# Quadrature_Decoder.net
KiCad netlist of a schematic drawn in Altium Designer
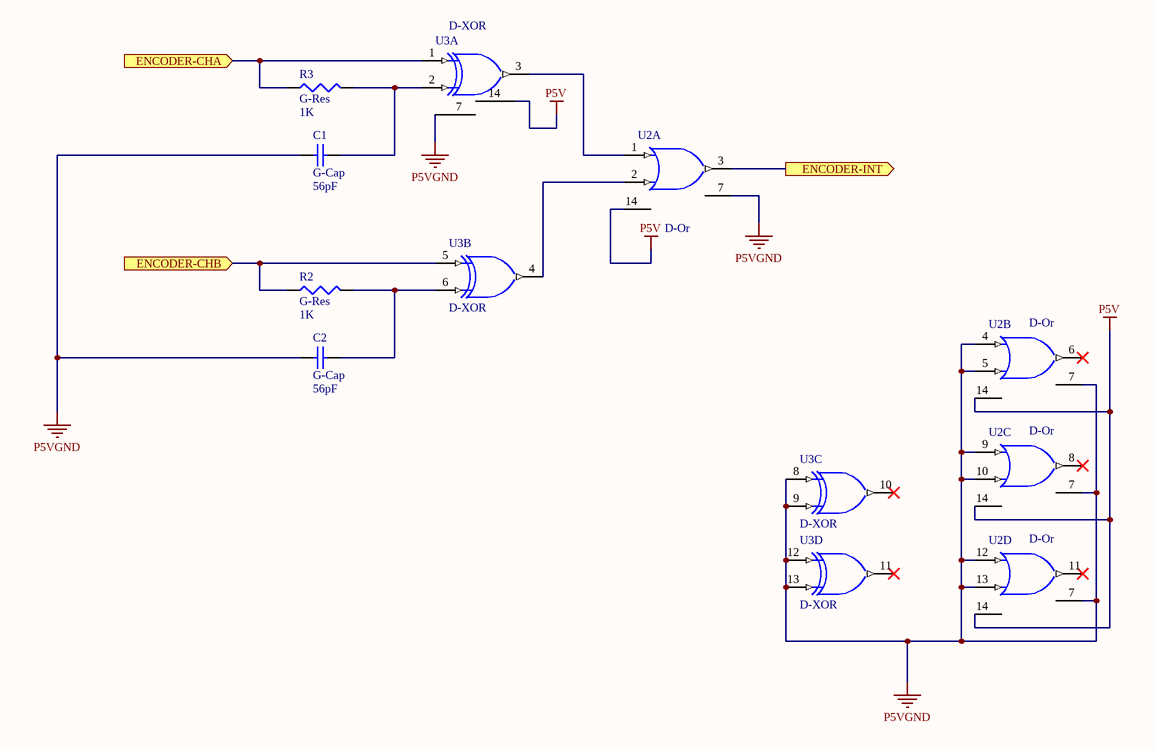
[diagram p0: Quadrature Decoder.SchDoc]

(export (version "E")
  (design (tool "Eeschema 10.0.6"))
  (components
    (comp (ref "C1")
      (value "G-Cap")
      (footprint "Cap2.54mm_LGE1.0")
      (description "capacitor (specify value)")
      (fields (field (name "ALTIUM_VALUE") "56pF") (field (name "PUBLISHER") "Altium Limited"))
      (libsource (lib "PartsDatabaseV13p4") (part "G-Cap"))
    )
    (comp (ref "C2")
      (value "G-Cap")
      (footprint "Cap2.54mm_LGE1.0")
      (description "capacitor (specify value)")
      (fields (field (name "ALTIUM_VALUE") "56pF") (field (name "PUBLISHER") "Altium Limited"))
      (libsource (lib "PartsDatabaseV13p4") (part "G-Cap"))
    )
    (comp (ref "R2")
      (value "G-Res")
      (footprint "Res2.54mm_LGE1.0")
      (description "resistor (specify value)")
      (fields (field (name "ALTIUM_VALUE") "1K") (field (name "PUBLISHER") "Altium Limited"))
      (libsource (lib "PartsDatabaseV13p4") (part "G-Res"))
    )
    (comp (ref "R3")
      (value "G-Res")
      (footprint "Res2.54mm_LGE1.0")
      (description "resistor (specify value)")
      (fields (field (name "ALTIUM_VALUE") "1K") (field (name "PUBLISHER") "Altium Limited"))
      (libsource (lib "PartsDatabaseV13p4") (part "G-Res"))
    )
    (comp (ref "U2")
      (value "D-Or")
      (footprint "DIP14_LGE1.0")
      (description "quad 2-input OR gate")
      (fields (field (name "PUBLISHER") "Altium Limited"))
      (libsource (lib "PartsDatabaseV13p4") (part "D-Or"))
    )
    (comp (ref "U3")
      (value "D-XOR")
      (footprint "DIP14_LGE1.0")
      (description "CD4070B")
      (libsource (lib "PartsDatabaseV13p4") (part "D-XOR"))
    )
  )
  (nets
    (net (code "1") (name "/ENCODER-CHA") (class "Default")
      (node (ref "R3") (pin "1") (pinfunction "1_1") (pintype "passive"))
      (node (ref "U3") (pin "1") (pinfunction "A_1") (pintype "input"))
    )
    (net (code "2") (name "/ENCODER-CHB") (class "Default")
      (node (ref "R2") (pin "1") (pinfunction "1_1") (pintype "passive"))
      (node (ref "U3") (pin "5") (pinfunction "C_5") (pintype "input"))
    )
    (net (code "3") (name "/ENCODER-INT") (class "Default")
      (node (ref "U2") (pin "3") (pinfunction "Y_3") (pintype "output"))
    )
    (net (code "4") (name "Net-(U2A-A)") (class "Default")
      (node (ref "U2") (pin "1") (pinfunction "A_1") (pintype "input"))
      (node (ref "U3") (pin "3") (pinfunction "J_3") (pintype "output"))
    )
    (net (code "5") (name "Net-(U2A-B)") (class "Default")
      (node (ref "U2") (pin "2") (pinfunction "B_2") (pintype "input"))
      (node (ref "U3") (pin "4") (pinfunction "K_4") (pintype "output"))
    )
    (net (code "6") (name "Net-(U3A-B)") (class "Default")
      (node (ref "C1") (pin "2") (pinfunction "2_2") (pintype "passive"))
      (node (ref "R3") (pin "2") (pinfunction "2_2") (pintype "passive"))
      (node (ref "U3") (pin "2") (pinfunction "B_2") (pintype "input"))
    )
    (net (code "7") (name "Net-(U3B-D)") (class "Default")
      (node (ref "C2") (pin "2") (pinfunction "2_2") (pintype "passive"))
      (node (ref "R2") (pin "2") (pinfunction "2_2") (pintype "passive"))
      (node (ref "U3") (pin "6") (pinfunction "D_6") (pintype "input"))
    )
    (net (code "8") (name "P5V") (class "Default")
      (node (ref "U2") (pin "14") (pinfunction "VCC_14") (pintype "power_in"))
      (node (ref "U3") (pin "14") (pinfunction "VCC_14") (pintype "power_in"))
    )
    (net (code "9") (name "P5VGND") (class "Default")
      (node (ref "C1") (pin "1") (pinfunction "1_1") (pintype "passive"))
      (node (ref "C2") (pin "1") (pinfunction "1_1") (pintype "passive"))
      (node (ref "U2") (pin "10") (pinfunction "B_10") (pintype "input"))
      (node (ref "U2") (pin "12") (pinfunction "A_12") (pintype "input"))
      (node (ref "U2") (pin "13") (pinfunction "B_13") (pintype "input"))
      (node (ref "U2") (pin "4") (pinfunction "A_4") (pintype "input"))
      (node (ref "U2") (pin "5") (pinfunction "B_5") (pintype "input"))
      (node (ref "U2") (pin "7") (pinfunction "GND_7") (pintype "power_in"))
      (node (ref "U2") (pin "9") (pinfunction "A_9") (pintype "input"))
      (node (ref "U3") (pin "12") (pinfunction "G_12") (pintype "input"))
      (node (ref "U3") (pin "13") (pinfunction "H_13") (pintype "input"))
      (node (ref "U3") (pin "7") (pinfunction "GND_7") (pintype "power_in"))
      (node (ref "U3") (pin "8") (pinfunction "E_8") (pintype "input"))
      (node (ref "U3") (pin "9") (pinfunction "F_9") (pintype "input"))
    )
    (net (code "10") (name "unconnected-(U2B-Y-Pad6)") (class "Default")
      (node (ref "U2") (pin "6") (pinfunction "Y_6") (pintype "output+no_connect"))
    )
    (net (code "11") (name "unconnected-(U2C-Y-Pad8)") (class "Default")
      (node (ref "U2") (pin "8") (pinfunction "Y_8") (pintype "output+no_connect"))
    )
    (net (code "12") (name "unconnected-(U2D-Y-Pad11)") (class "Default")
      (node (ref "U2") (pin "11") (pinfunction "Y_11") (pintype "output+no_connect"))
    )
    (net (code "13") (name "unconnected-(U3C-L-Pad10)") (class "Default")
      (node (ref "U3") (pin "10") (pinfunction "L_10") (pintype "output+no_connect"))
    )
    (net (code "14") (name "unconnected-(U3D-M-Pad11)") (class "Default")
      (node (ref "U3") (pin "11") (pinfunction "M_11") (pintype "output+no_connect"))
    )
  )
)
